# mppt_charger_sch.net
KiCad netlist of a schematic drawn in Altium Designer
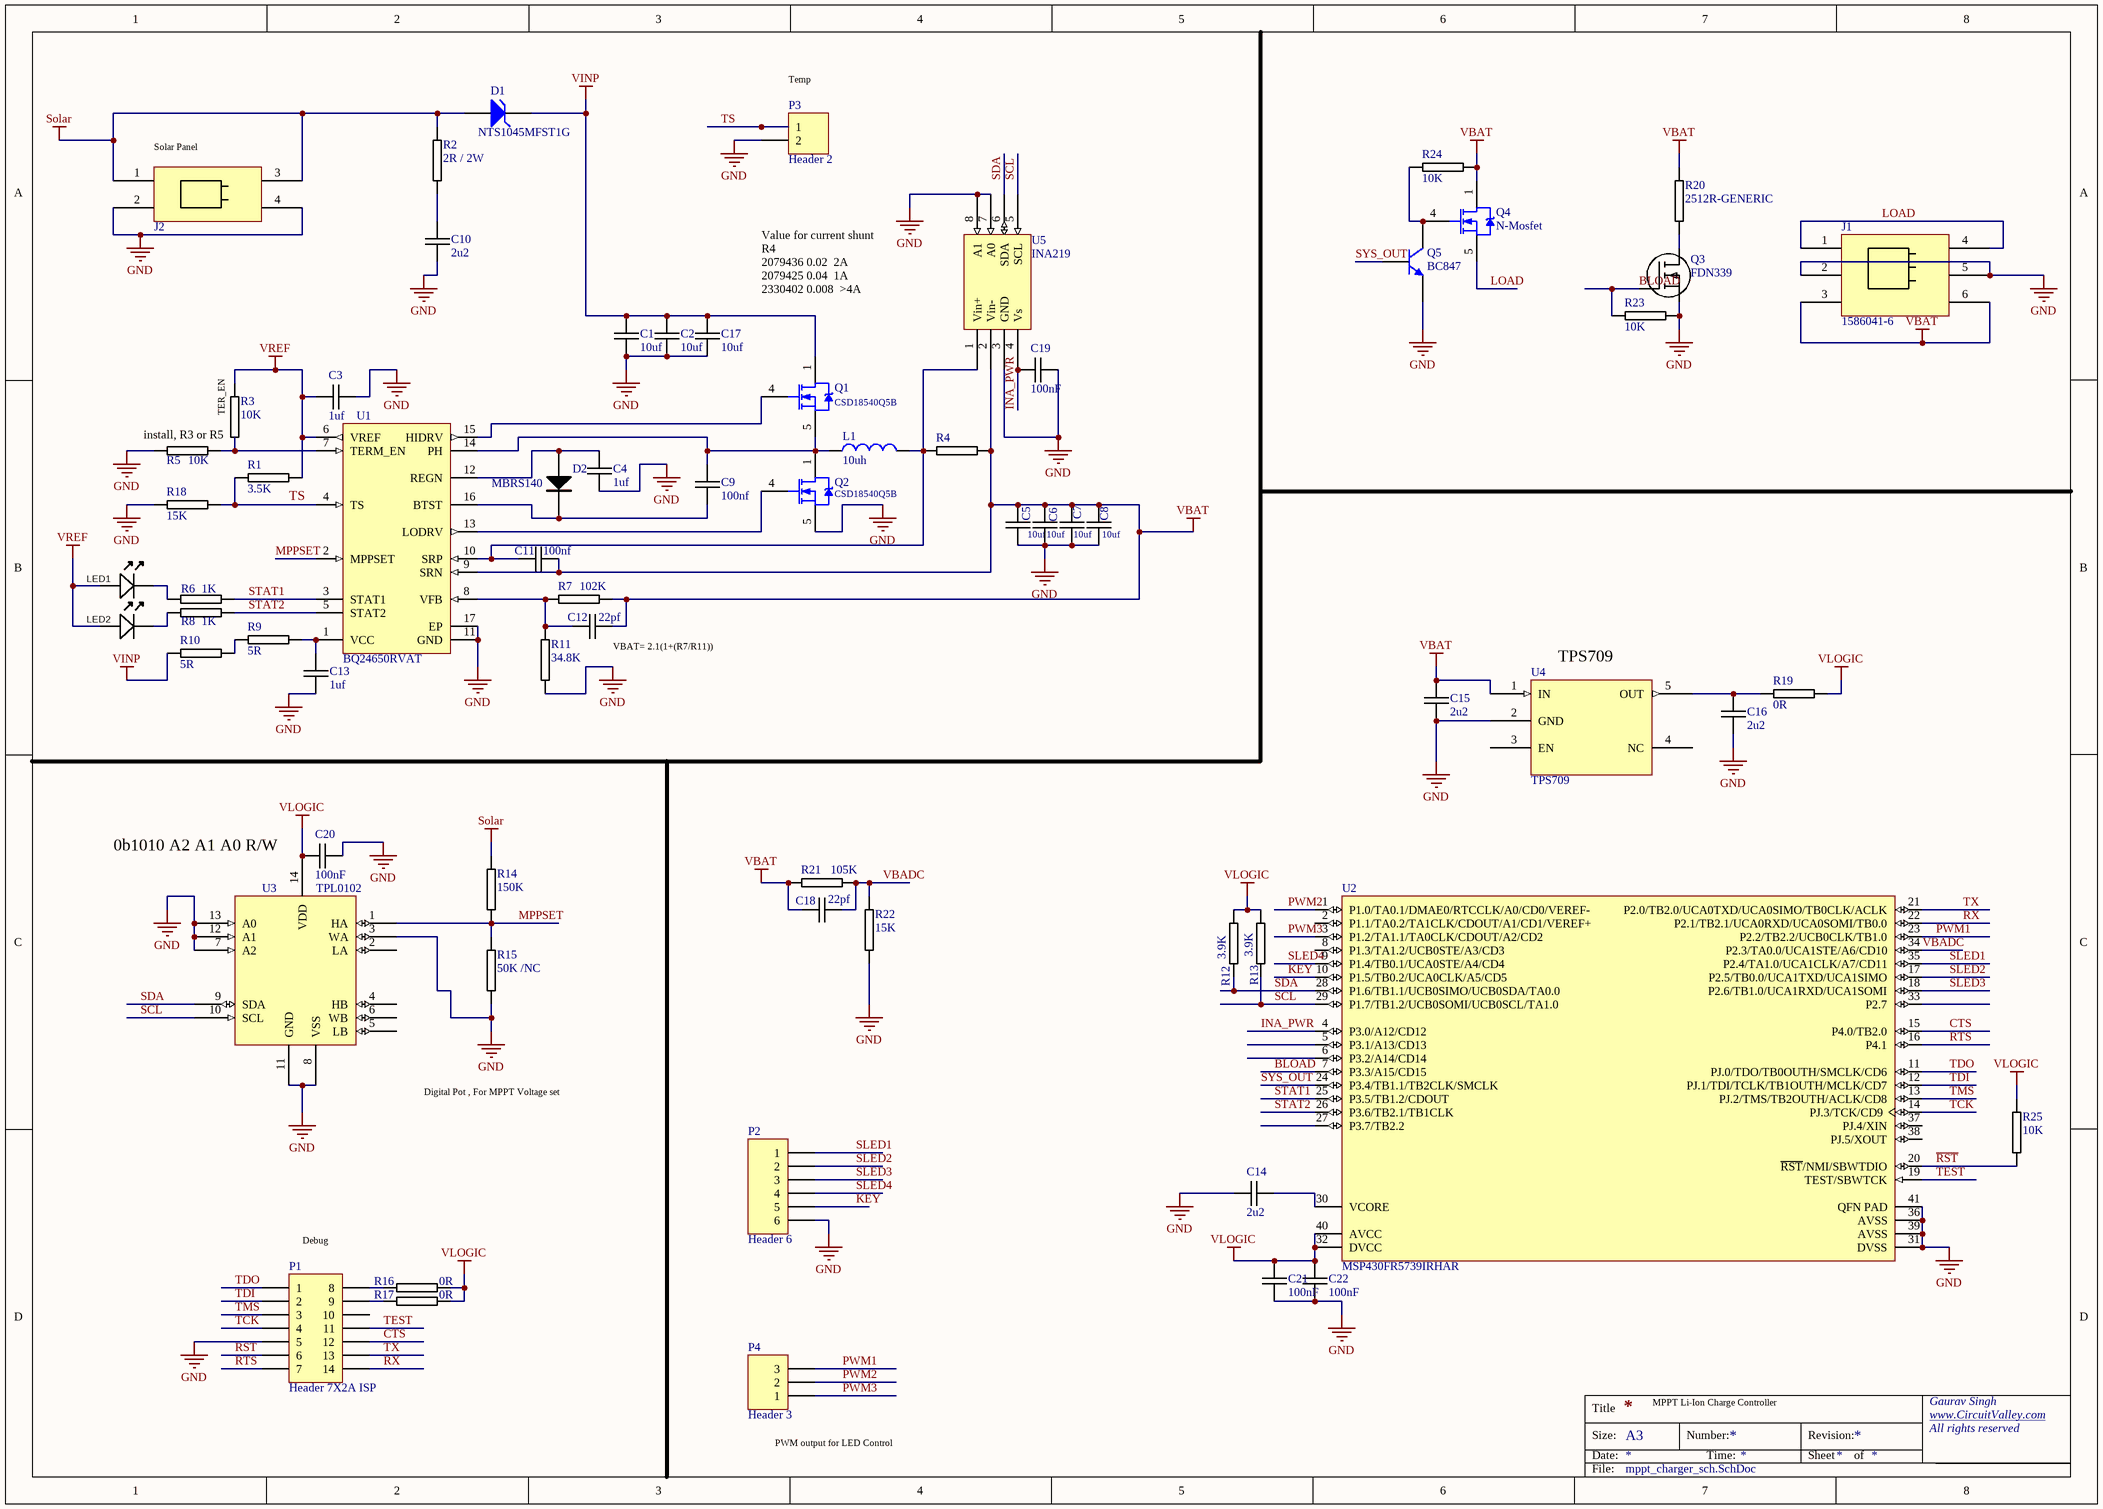
[diagram p0: mppt_charger_sch.SchDoc]

(export (version "E")
  (design (tool "Eeschema 10.0.6"))
  (components
    (comp (ref "C1")
      (value "10uf")
      (footprint "1210C-GENERIC")
      (description "GENERIC CAPACITOR NON POLARISED 1210")
      (fields
        (field (name "MANUFACTURER") "Panasonic - ECG")
        (field (name "MANUFACTURER PART NUMBER") "ECJ-4YB0J226M")
      )
      (libsource (lib "Generic") (part "1210C-2u2-35V"))
    )
    (comp (ref "C2")
      (value "10uf")
      (footprint "1210C-GENERIC")
      (description "GENERIC CAPACITOR NON POLARISED 1210")
      (fields
        (field (name "MANUFACTURER") "Panasonic - ECG")
        (field (name "MANUFACTURER PART NUMBER") "ECJ-4YB0J226M")
      )
      (libsource (lib "Generic") (part "1210C-2u2-35V"))
    )
    (comp (ref "C3")
      (value "1uf")
      (footprint "0805C-GENERIC")
      (description "CAPACITOR 0805 CERAMIC")
      (fields
        (field (name "MANUFACTURER PART NUMBER") "ECJ-1VB0J225K")
        (field (name "MANUFACTURER") "Panasonic - ECG")
      )
      (libsource (lib "Generic") (part "0805C-2U2-6V3-X5R-PAN"))
    )
    (comp (ref "C4")
      (value "1uf")
      (footprint "0805C-GENERIC")
      (description "CAPACITOR 0805 CERAMIC")
      (fields
        (field (name "MANUFACTURER PART NUMBER") "ECJ-1VB0J225K")
        (field (name "MANUFACTURER") "Panasonic - ECG")
      )
      (libsource (lib "Generic") (part "0805C-2U2-6V3-X5R-PAN"))
    )
    (comp (ref "C5")
      (value "10uf")
      (footprint "1210C-GENERIC")
      (description "GENERIC CAPACITOR NON POLARISED 1210")
      (fields
        (field (name "MANUFACTURER") "Panasonic - ECG")
        (field (name "MANUFACTURER PART NUMBER") "ECJ-4YB0J226M")
      )
      (libsource (lib "Generic") (part "1210C-2u2-35V"))
    )
    (comp (ref "C6")
      (value "10uf")
      (footprint "1210C-GENERIC")
      (description "GENERIC CAPACITOR NON POLARISED 1210")
      (fields
        (field (name "MANUFACTURER") "Panasonic - ECG")
        (field (name "MANUFACTURER PART NUMBER") "ECJ-4YB0J226M")
      )
      (libsource (lib "Generic") (part "1210C-2u2-35V"))
    )
    (comp (ref "C7")
      (value "10uf")
      (footprint "1210C-GENERIC")
      (description "GENERIC CAPACITOR NON POLARISED 1210")
      (fields
        (field (name "MANUFACTURER") "Panasonic - ECG")
        (field (name "MANUFACTURER PART NUMBER") "ECJ-4YB0J226M")
      )
      (libsource (lib "Generic") (part "1210C-2u2-35V"))
    )
    (comp (ref "C8")
      (value "10uf")
      (footprint "1210C-GENERIC")
      (description "GENERIC CAPACITOR NON POLARISED 1210")
      (fields
        (field (name "MANUFACTURER") "Panasonic - ECG")
        (field (name "MANUFACTURER PART NUMBER") "ECJ-4YB0J226M")
      )
      (libsource (lib "Generic") (part "1210C-2u2-35V"))
    )
    (comp (ref "C9")
      (value "100nf")
      (footprint "0805C-GENERIC")
      (description "CAPACITOR 0805 CERAMIC")
      (fields
        (field (name "MANUFACTURER PART NUMBER") "ECJ-1VB0J225K")
        (field (name "MANUFACTURER") "Panasonic - ECG")
      )
      (libsource (lib "Generic") (part "0805C-2U2-6V3-X5R-PAN"))
    )
    (comp (ref "C10")
      (value "2u2")
      (footprint "1210C-GENERIC")
      (description "GENERIC CAPACITOR NON POLARISED 1210")
      (fields
        (field (name "MANUFACTURER") "Panasonic - ECG")
        (field (name "MANUFACTURER PART NUMBER") "ECJ-4YB0J226M")
      )
      (libsource (lib "Generic") (part "1210C-2u2-35V"))
    )
    (comp (ref "C11")
      (value "100nf")
      (footprint "0805C-GENERIC")
      (description "CAPACITOR 0805 CERAMIC")
      (fields
        (field (name "MANUFACTURER PART NUMBER") "ECJ-1VB0J225K")
        (field (name "MANUFACTURER") "Panasonic - ECG")
      )
      (libsource (lib "Generic") (part "0805C-2U2-6V3-X5R-PAN"))
    )
    (comp (ref "C12")
      (value "22pf")
      (footprint "0805C-GENERIC")
      (description "CAPACITOR 0805 CERAMIC")
      (fields
        (field (name "MANUFACTURER PART NUMBER") "ECJ-1VB0J225K")
        (field (name "MANUFACTURER") "Panasonic - ECG")
      )
      (libsource (lib "Generic") (part "0805C-2U2-6V3-X5R-PAN"))
    )
    (comp (ref "C13")
      (value "1uf")
      (footprint "0805C-TBD")
      (description "CAPACITOR 0805 CERAMIC VALUE TO BE DETERMINED")
      (libsource (lib "Generic") (part "0805C-TBD"))
    )
    (comp (ref "C14")
      (value "2u2")
      (footprint "0805C-GENERIC")
      (description "CAPACITOR 0805 CERAMIC")
      (fields
        (field (name "MANUFACTURER PART NUMBER") "ECJ-1VB0J225K")
        (field (name "MANUFACTURER") "Panasonic - ECG")
      )
      (libsource (lib "Generic") (part "0805C-2U2-6V3-X5R-PAN"))
    )
    (comp (ref "C15")
      (value "2u2")
      (footprint "1210C-GENERIC")
      (description "GENERIC CAPACITOR NON POLARISED 1210")
      (fields
        (field (name "MANUFACTURER") "Panasonic - ECG")
        (field (name "MANUFACTURER PART NUMBER") "ECJ-4YB0J226M")
      )
      (libsource (lib "Generic") (part "1210C-2u2-35V"))
    )
    (comp (ref "C16")
      (value "2u2")
      (footprint "1210C-GENERIC")
      (description "GENERIC CAPACITOR NON POLARISED 1210")
      (fields
        (field (name "MANUFACTURER") "Panasonic - ECG")
        (field (name "MANUFACTURER PART NUMBER") "ECJ-4YB0J226M")
      )
      (libsource (lib "Generic") (part "1210C-2u2-35V"))
    )
    (comp (ref "C17")
      (value "10uf")
      (footprint "1210C-GENERIC")
      (description "GENERIC CAPACITOR NON POLARISED 1210")
      (fields
        (field (name "MANUFACTURER") "Panasonic - ECG")
        (field (name "MANUFACTURER PART NUMBER") "ECJ-4YB0J226M")
      )
      (libsource (lib "Generic") (part "1210C-2u2-35V"))
    )
    (comp (ref "C18")
      (value "22pf")
      (footprint "0805C-GENERIC")
      (description "CAPACITOR 0805 CERAMIC")
      (fields
        (field (name "MANUFACTURER PART NUMBER") "ECJ-1VB0J225K")
        (field (name "MANUFACTURER") "Panasonic - ECG")
      )
      (libsource (lib "Generic") (part "0805C-2U2-6V3-X5R-PAN"))
    )
    (comp (ref "C19")
      (value "100nF")
      (footprint "0603C-GENERIC")
      (description "CAPACITOR 0603 CERAMIC")
      (fields
        (field (name "MANUFACTURER PART NUMBER") "C1608X7R1E104K")
        (field (name "MANUFACTURER") "TDK Corporation")
      )
      (libsource (lib "Generic") (part "0603C-100NF-25V-X7R-TDK"))
    )
    (comp (ref "C20")
      (value "100nF")
      (footprint "0603C-GENERIC")
      (description "CAPACITOR 0603 CERAMIC")
      (fields
        (field (name "MANUFACTURER PART NUMBER") "C1608X7R1E104K")
        (field (name "MANUFACTURER") "TDK Corporation")
      )
      (libsource (lib "Generic") (part "0603C-100NF-25V-X7R-TDK"))
    )
    (comp (ref "C21")
      (value "100nF")
      (footprint "0603C-GENERIC")
      (description "CAPACITOR 0603 CERAMIC")
      (fields
        (field (name "MANUFACTURER PART NUMBER") "C1608X7R1E104K")
        (field (name "MANUFACTURER") "TDK Corporation")
      )
      (libsource (lib "Generic") (part "0603C-100NF-25V-X7R-TDK"))
    )
    (comp (ref "C22")
      (value "100nF")
      (footprint "0603C-GENERIC")
      (description "CAPACITOR 0603 CERAMIC")
      (fields
        (field (name "MANUFACTURER PART NUMBER") "C1608X7R1E104K")
        (field (name "MANUFACTURER") "TDK Corporation")
      )
      (libsource (lib "Generic") (part "0603C-100NF-25V-X7R-TDK"))
    )
    (comp (ref "D1") (value "NTS1045MFST1G") (footprint "DFN5_5x6") (libsource (lib "diode") (part "SK3200")))
    (comp (ref "D2")
      (value "MBRS140")
      (footprint "DIODE-SMA")
      (description "DIODE")
      (libsource (lib "Generic") (part "MBRS140"))
    )
    (comp (ref "J1")
      (value "1586041-6")
      (footprint "1586043-6")
      (libsource (lib "power_connector") (part "1586041-6"))
    )
    (comp (ref "J2")
      (value "1586041-4")
      (footprint "1586043-4")
      (libsource (lib "power_connector") (part "1586041-4"))
    )
    (comp (ref "L1") (value "10uh") (footprint "SRP1238A") (libsource (lib "Inductor") (part "inductor_smd")))
    (comp (ref "LED1")
      (value "~")
      (footprint "LED-0805-K")
      (description "LED, 0805 SMD, Green")
      (libsource (lib "PBL - Light Sources") (part "LED_SMD_Green_0805"))
    )
    (comp (ref "LED2")
      (value "~")
      (footprint "LED-0805-K")
      (description "LED, 0805 SMD, Green")
      (libsource (lib "PBL - Light Sources") (part "LED_SMD_Green_0805"))
    )
    (comp (ref "P1")
      (value "Header 7X2A ISP")
      (footprint "HDR2X7_CEN")
      (description "Header, 7-Pin, Dual row")
      (fields (field (name "PUBLISHER") "Altium Limited"))
      (libsource (lib "Miscellaneous Connectors") (part "Header 7X2A"))
    )
    (comp (ref "P2")
      (value "Header 6")
      (footprint "5267-06A")
      (description "Header, 6-Pin")
      (fields (field (name "PUBLISHER") "Altium Limited"))
      (libsource (lib "Miscellaneous Connectors") (part "Header 6"))
    )
    (comp (ref "P3")
      (value "Header 2")
      (footprint "5267-02A")
      (description "Header, 2-Pin")
      (fields (field (name "PUBLISHER") "Altium Limited"))
      (libsource (lib "Miscellaneous Connectors") (part "Header 2"))
    )
    (comp (ref "P4")
      (value "Header 3")
      (footprint "5267-03A")
      (description "Header, 3-Pin")
      (fields (field (name "PUBLISHER") "Altium Limited"))
      (libsource (lib "Miscellaneous Connectors") (part "Header 3"))
    )
    (comp (ref "Q1") (value "CSD18540Q5B") (footprint "SON8") (libsource (lib "mosfet") (part "N-Mosfet")))
    (comp (ref "Q2") (value "CSD18540Q5B") (footprint "SON8") (libsource (lib "mosfet") (part "N-Mosfet")))
    (comp (ref "Q3")
      (value "FDN339")
      (footprint "SOT23-GDS")
      (description "N-MOS TRANSISTOR FDN339")
      (fields
        (field (name "MANUFACTURER") "Fairchild Semiconductor")
        (field (name "MANUFACTURER PART NUMBER") "FDN339AN")
      )
      (libsource (lib "Generic") (part "FDN339"))
    )
    (comp (ref "Q4") (value "N-Mosfet") (footprint "SON8") (libsource (lib "mosfet") (part "N-Mosfet")))
    (comp (ref "Q5")
      (value "BC847")
      (footprint "SOT23_N")
      (description "NPN General-purpose Transistor")
      (fields (field (name "PUBLISHER") "Altium Limited"))
      (libsource (lib "Philips Discrete BJT - Low Power") (part "BC847"))
    )
    (comp (ref "R1")
      (value "3.5K")
      (footprint "0805R-2K2")
      (description "RESISTOR 0805 1/4 WATT THIN FILM")
      (libsource (lib "Generic") (part "0805R-2K2"))
    )
    (comp (ref "R2")
      (value "2R / 2W")
      (footprint "2512R-GENERIC")
      (description "GENERIC RESISTOR 2512")
      (libsource (lib "Generic") (part "2512R-GENERIC"))
    )
    (comp (ref "R3")
      (value "10K")
      (footprint "0805R-2K2")
      (description "RESISTOR 0805 1/4 WATT THIN FILM")
      (libsource (lib "Generic") (part "0805R-2K2"))
    )
    (comp (ref "R4")
      (value "~")
      (footprint "2512R-GENERIC")
      (description "GENERIC RESISTOR 2512")
      (libsource (lib "Generic") (part "2512R-GENERIC"))
    )
    (comp (ref "R5")
      (value "10K")
      (footprint "0805R-2K2")
      (description "RESISTOR 0805 1/4 WATT THIN FILM")
      (libsource (lib "Generic") (part "0805R-2K2"))
    )
    (comp (ref "R6")
      (value "1K")
      (footprint "0805R-2K2")
      (description "RESISTOR 0805 1/4 WATT THIN FILM")
      (libsource (lib "Generic") (part "0805R-2K2"))
    )
    (comp (ref "R7")
      (value "102K")
      (footprint "0805R-2K2")
      (description "RESISTOR 0805 1/4 WATT THIN FILM")
      (libsource (lib "Generic") (part "0805R-2K2"))
    )
    (comp (ref "R8")
      (value "1K")
      (footprint "0805R-2K2")
      (description "RESISTOR 0805 1/4 WATT THIN FILM")
      (libsource (lib "Generic") (part "0805R-2K2"))
    )
    (comp (ref "R9")
      (value "5R")
      (footprint "0805R-2K2")
      (description "RESISTOR 0805 1/4 WATT THIN FILM")
      (libsource (lib "Generic") (part "0805R-2K2"))
    )
    (comp (ref "R10")
      (value "5R")
      (footprint "0805R-2K2")
      (description "RESISTOR 0805 1/4 WATT THIN FILM")
      (libsource (lib "Generic") (part "0805R-2K2"))
    )
    (comp (ref "R11")
      (value "34.8K")
      (footprint "0805R-2K2")
      (description "RESISTOR 0805 1/4 WATT THIN FILM")
      (libsource (lib "Generic") (part "0805R-2K2"))
    )
    (comp (ref "R12")
      (value "3.9K")
      (footprint "0805R-2K2")
      (description "RESISTOR 0805 1/4 WATT THIN FILM")
      (libsource (lib "Generic") (part "0805R-2K2"))
    )
    (comp (ref "R13")
      (value "3.9K")
      (footprint "0805R-2K2")
      (description "RESISTOR 0805 1/4 WATT THIN FILM")
      (libsource (lib "Generic") (part "0805R-2K2"))
    )
    (comp (ref "R14")
      (value "150K")
      (footprint "0805R-2K2")
      (description "RESISTOR 0805 1/4 WATT THIN FILM")
      (libsource (lib "Generic") (part "0805R-2K2"))
    )
    (comp (ref "R15")
      (value "50K /NC")
      (footprint "0805R-2K2")
      (description "RESISTOR 0805 1/4 WATT THIN FILM")
      (libsource (lib "Generic") (part "0805R-2K2"))
    )
    (comp (ref "R16")
      (value "0R")
      (footprint "0805R-2K2")
      (description "RESISTOR 0805 1/4 WATT THIN FILM")
      (libsource (lib "Generic") (part "0805R-2K2"))
    )
    (comp (ref "R17")
      (value "0R")
      (footprint "0805R-2K2")
      (description "RESISTOR 0805 1/4 WATT THIN FILM")
      (libsource (lib "Generic") (part "0805R-2K2"))
    )
    (comp (ref "R18")
      (value "15K")
      (footprint "0805R-2K2")
      (description "RESISTOR 0805 1/4 WATT THIN FILM")
      (libsource (lib "Generic") (part "0805R-2K2"))
    )
    (comp (ref "R19")
      (value "0R")
      (footprint "0805R-2K2")
      (description "RESISTOR 0805 1/4 WATT THIN FILM")
      (libsource (lib "Generic") (part "0805R-2K2"))
    )
    (comp (ref "R20")
      (value "2512R-GENERIC")
      (footprint "2512R-GENERIC")
      (description "GENERIC RESISTOR 2512")
      (libsource (lib "Generic") (part "2512R-GENERIC"))
    )
    (comp (ref "R21")
      (value "105K")
      (footprint "0805R-2K2")
      (description "RESISTOR 0805 1/4 WATT THIN FILM")
      (libsource (lib "Generic") (part "0805R-2K2"))
    )
    (comp (ref "R22")
      (value "15K")
      (footprint "0805R-2K2")
      (description "RESISTOR 0805 1/4 WATT THIN FILM")
      (libsource (lib "Generic") (part "0805R-2K2"))
    )
    (comp (ref "R23")
      (value "10K")
      (footprint "0603R-10K")
      (description "GENERIC RESISTOR 0603")
      (fields (field (name "MANUFACTURER") "Stackpole Electronics Inc") (field (name "TOLERANCE") "±1%"))
      (libsource (lib "Generic") (part "0603R-10K"))
    )
    (comp (ref "R24")
      (value "10K")
      (footprint "0603R-10K")
      (description "GENERIC RESISTOR 0603")
      (fields (field (name "MANUFACTURER") "Stackpole Electronics Inc") (field (name "TOLERANCE") "±1%"))
      (libsource (lib "Generic") (part "0603R-10K"))
    )
    (comp (ref "R25")
      (value "10K")
      (footprint "0603R-10K")
      (description "GENERIC RESISTOR 0603")
      (fields (field (name "MANUFACTURER") "Stackpole Electronics Inc") (field (name "TOLERANCE") "±1%"))
      (libsource (lib "Generic") (part "0603R-10K"))
    )
    (comp (ref "U1")
      (value "BQ24650RVAT")
      (footprint "QFN16")
      (fields (field (name "MANUFACTURER") "Texas Instruments"))
      (libsource (lib "TI Power Management Battery Management") (part "BQ24650RVAT"))
    )
    (comp (ref "U2")
      (value "MSP430FR5739IRHAR")
      (footprint "QFN40")
      (fields (field (name "MANUFACTURER") "Texas Instruments"))
      (libsource (lib "TI Microcontroller MSP430 16-bit Ultra-Low Power") (part "MSP430FR5739IRHAR"))
    )
    (comp (ref "U3")
      (value "TPL0102")
      (footprint "XQFN14_2mmx2mm")
      (description "Digital Pot 2 channel 256 setp nov volatile memeory")
      (libsource (lib "digital_pot") (part "TPL0102"))
    )
    (comp (ref "U4") (value "TPS709") (footprint "SOT23-5") (libsource (lib "LDO_reg") (part "TPS709")))
    (comp (ref "U5")
      (value "INA219")
      (footprint "SOT23-8")
      (libsource (lib "INA219-SOT23-8") (part "INA219"))
    )
  )
  (nets
    (net (code "1") (name "/BLOAD") (class "Default")
      (node (ref "Q3") (pin "G") (pinfunction "G_G") (pintype "passive"))
      (node (ref "R23") (pin "2") (pintype "passive"))
      (node (ref "U2") (pin "7") (pinfunction "P3.3/A15/CD15_7") (pintype "bidirectional"))
    )
    (net (code "2") (name "/CTS") (class "Default")
      (node (ref "P1") (pin "12") (pinfunction "12_12") (pintype "passive"))
      (node (ref "U2") (pin "15") (pinfunction "P4.0/TB2.0_15") (pintype "bidirectional"))
    )
    (net (code "3") (name "/INA_PWR") (class "Default")
      (node (ref "C19") (pin "2") (pintype "passive"))
      (node (ref "U2") (pin "4") (pinfunction "P3.0/A12/CD12_4") (pintype "bidirectional"))
      (node (ref "U5") (pin "4") (pinfunction "Vs_4") (pintype "power_in"))
    )
    (net (code "4") (name "/KEY") (class "Default")
      (node (ref "P2") (pin "5") (pinfunction "5_5") (pintype "passive"))
      (node (ref "U2") (pin "10") (pinfunction "P1.5/TB0.2/UCA0CLK/A5/CD5_10") (pintype "bidirectional"))
    )
    (net (code "5") (name "/LOAD") (class "Default")
      (node (ref "J1") (pin "1") (pinfunction "IN_1") (pintype "passive"))
      (node (ref "J1") (pin "4") (pinfunction "IN_4") (pintype "passive"))
      (node (ref "Q4") (pin "5") (pinfunction "S_5") (pintype "passive"))
    )
    (net (code "6") (name "/MPPSET") (class "Default")
      (node (ref "R14") (pin "1") (pintype "passive"))
      (node (ref "R15") (pin "2") (pintype "passive"))
      (node (ref "U1") (pin "2") (pinfunction "MPPSET_2") (pintype "input"))
      (node (ref "U3") (pin "1") (pinfunction "HA_1") (pintype "bidirectional"))
    )
    (net (code "7") (name "/PWM1") (class "Default")
      (node (ref "P4") (pin "3") (pinfunction "3_3") (pintype "passive"))
      (node (ref "U2") (pin "23") (pinfunction "P2.2/TB2.2/UCB0CLK/TB1.0_23") (pintype "bidirectional"))
    )
    (net (code "8") (name "/PWM2") (class "Default")
      (node (ref "P4") (pin "2") (pinfunction "2_2") (pintype "passive"))
      (node (ref "U2") (pin "1") (pinfunction "P1.0/TA0.1/DMAE0/RTCCLK/A0/CD0/VEREF-_1") (pintype "bidirectional"))
    )
    (net (code "9") (name "/PWM3") (class "Default")
      (node (ref "P4") (pin "1") (pinfunction "1_1") (pintype "passive"))
      (node (ref "U2") (pin "3") (pinfunction "P1.2/TA1.1/TA0CLK/CDOUT/A2/CD2_3") (pintype "bidirectional"))
    )
    (net (code "10") (name "/RTS") (class "Default")
      (node (ref "P1") (pin "7") (pinfunction "7_7") (pintype "passive"))
      (node (ref "U2") (pin "16") (pinfunction "P4.1_16") (pintype "bidirectional"))
    )
    (net (code "11") (name "/RX") (class "Default")
      (node (ref "P1") (pin "14") (pinfunction "14_14") (pintype "passive"))
      (node (ref "U2") (pin "22") (pinfunction "P2.1/TB2.1/UCA0RXD/UCA0SOMI/TB0.0_22") (pintype "bidirectional"))
    )
    (net (code "12") (name "/SCL") (class "Default")
      (node (ref "R13") (pin "1") (pintype "passive"))
      (node (ref "U2") (pin "29") (pinfunction "P1.7/TB1.2/UCB0SOMI/UCB0SCL/TA1.0_29") (pintype "bidirectional"))
      (node (ref "U3") (pin "10") (pinfunction "SCL_10") (pintype "input"))
      (node (ref "U5") (pin "5") (pinfunction "SCL_5") (pintype "input"))
    )
    (net (code "13") (name "/SDA") (class "Default")
      (node (ref "R12") (pin "1") (pintype "passive"))
      (node (ref "U2") (pin "28") (pinfunction "P1.6/TB1.1/UCB0SIMO/UCB0SDA/TA0.0_28") (pintype "bidirectional"))
      (node (ref "U3") (pin "9") (pinfunction "SDA_9") (pintype "bidirectional"))
      (node (ref "U5") (pin "6") (pinfunction "SDA_6") (pintype "bidirectional"))
    )
    (net (code "14") (name "/SLED1") (class "Default")
      (node (ref "P2") (pin "1") (pinfunction "1_1") (pintype "passive"))
      (node (ref "U2") (pin "35") (pinfunction "P2.4/TA1.0/UCA1CLK/A7/CD11_35") (pintype "bidirectional"))
    )
    (net (code "15") (name "/SLED2") (class "Default")
      (node (ref "P2") (pin "2") (pinfunction "2_2") (pintype "passive"))
      (node (ref "U2") (pin "17") (pinfunction "P2.5/TB0.0/UCA1TXD/UCA1SIMO_17") (pintype "bidirectional"))
    )
    (net (code "16") (name "/SLED3") (class "Default")
      (node (ref "P2") (pin "3") (pinfunction "3_3") (pintype "passive"))
      (node (ref "U2") (pin "18") (pinfunction "P2.6/TB1.0/UCA1RXD/UCA1SOMI_18") (pintype "bidirectional"))
    )
    (net (code "17") (name "/SLED4") (class "Default")
      (node (ref "P2") (pin "4") (pinfunction "4_4") (pintype "passive"))
      (node (ref "U2") (pin "9") (pinfunction "P1.4/TB0.1/UCA0STE/A4/CD4_9") (pintype "bidirectional"))
    )
    (net (code "18") (name "/STAT1") (class "Default")
      (node (ref "R6") (pin "2") (pintype "passive"))
      (node (ref "U1") (pin "3") (pinfunction "STAT1_3") (pintype "open_collector"))
      (node (ref "U2") (pin "25") (pinfunction "P3.5/TB1.2/CDOUT_25") (pintype "bidirectional"))
    )
    (net (code "19") (name "/STAT2") (class "Default")
      (node (ref "R8") (pin "2") (pintype "passive"))
      (node (ref "U1") (pin "5") (pinfunction "STAT2_5") (pintype "open_collector"))
      (node (ref "U2") (pin "26") (pinfunction "P3.6/TB2.1/TB1CLK_26") (pintype "bidirectional"))
    )
    (net (code "20") (name "/SYS_OUT") (class "Default")
      (node (ref "Q5") (pin "1") (pinfunction "B_1") (pintype "passive"))
      (node (ref "U2") (pin "24") (pinfunction "P3.4/TB1.1/TB2CLK/SMCLK_24") (pintype "bidirectional"))
    )
    (net (code "21") (name "/TCK") (class "Default")
      (node (ref "P1") (pin "4") (pinfunction "4_4") (pintype "passive"))
      (node (ref "U2") (pin "14") (pinfunction "PJ.3/TCK/CD9_14") (pintype "bidirectional"))
    )
    (net (code "22") (name "/TDI") (class "Default")
      (node (ref "P1") (pin "2") (pinfunction "2_2") (pintype "passive"))
      (node (ref "U2") (pin "12") (pinfunction "PJ.1/TDI/TCLK/TB1OUTH/MCLK/CD7_12") (pintype "bidirectional"))
    )
    (net (code "23") (name "/TDO") (class "Default")
      (node (ref "P1") (pin "1") (pinfunction "1_1") (pintype "passive"))
      (node (ref "U2") (pin "11") (pinfunction "PJ.0/TDO/TB0OUTH/SMCLK/CD6_11") (pintype "bidirectional"))
    )
    (net (code "24") (name "/TEST") (class "Default")
      (node (ref "P1") (pin "11") (pinfunction "11_11") (pintype "passive"))
      (node (ref "U2") (pin "19") (pinfunction "TEST/SBWTCK_19") (pintype "input"))
    )
    (net (code "25") (name "/TMS") (class "Default")
      (node (ref "P1") (pin "3") (pinfunction "3_3") (pintype "passive"))
      (node (ref "U2") (pin "13") (pinfunction "PJ.2/TMS/TB2OUTH/ACLK/CD8_13") (pintype "bidirectional"))
    )
    (net (code "26") (name "/TS") (class "Default")
      (node (ref "P3") (pin "1") (pinfunction "1_1") (pintype "passive"))
      (node (ref "R1") (pin "2") (pintype "passive"))
      (node (ref "R18") (pin "1") (pintype "passive"))
      (node (ref "U1") (pin "4") (pinfunction "TS_4") (pintype "input"))
    )
    (net (code "27") (name "/TX") (class "Default")
      (node (ref "P1") (pin "13") (pinfunction "13_13") (pintype "passive"))
      (node (ref "U2") (pin "21") (pinfunction "P2.0/TB2.0/UCA0TXD/UCA0SIMO/TB0CLK/ACLK_21") (pintype "bidirectional"))
    )
    (net (code "28") (name "/VBADC") (class "Default")
      (node (ref "C18") (pin "1") (pintype "passive"))
      (node (ref "R21") (pin "2") (pintype "passive"))
      (node (ref "R22") (pin "2") (pintype "passive"))
      (node (ref "U2") (pin "34") (pinfunction "P2.3/TA0.0/UCA1STE/A6/CD10_34") (pintype "bidirectional"))
    )
    (net (code "29") (name "/~{RST}") (class "Default")
      (node (ref "P1") (pin "6") (pinfunction "6_6") (pintype "passive"))
      (node (ref "R25") (pin "2") (pintype "passive"))
      (node (ref "U2") (pin "20") (pinfunction "~{RST}/NMI/SBWTDIO_20") (pintype "bidirectional"))
    )
    (net (code "30") (name "GND") (class "Default")
      (node (ref "C1") (pin "2") (pintype "passive"))
      (node (ref "C10") (pin "2") (pintype "passive"))
      (node (ref "C13") (pin "2") (pintype "passive"))
      (node (ref "C14") (pin "1") (pintype "passive"))
      (node (ref "C15") (pin "2") (pintype "passive"))
      (node (ref "C16") (pin "2") (pintype "passive"))
      (node (ref "C17") (pin "2") (pintype "passive"))
      (node (ref "C19") (pin "1") (pintype "passive"))
      (node (ref "C2") (pin "2") (pintype "passive"))
      (node (ref "C20") (pin "2") (pintype "passive"))
      (node (ref "C21") (pin "2") (pintype "passive"))
      (node (ref "C22") (pin "2") (pintype "passive"))
      (node (ref "C3") (pin "2") (pintype "passive"))
      (node (ref "C4") (pin "2") (pintype "passive"))
      (node (ref "C5") (pin "2") (pintype "passive"))
      (node (ref "C6") (pin "2") (pintype "passive"))
      (node (ref "C7") (pin "2") (pintype "passive"))
      (node (ref "C8") (pin "2") (pintype "passive"))
      (node (ref "J1") (pin "2") (pinfunction "IN_2") (pintype "passive"))
      (node (ref "J1") (pin "5") (pinfunction "5_5") (pintype "passive"))
      (node (ref "J2") (pin "2") (pinfunction "IN_2") (pintype "passive"))
      (node (ref "J2") (pin "4") (pinfunction "IN_4") (pintype "passive"))
      (node (ref "P1") (pin "5") (pinfunction "5_5") (pintype "passive"))
      (node (ref "P2") (pin "6") (pinfunction "6_6") (pintype "passive"))
      (node (ref "P3") (pin "2") (pinfunction "2_2") (pintype "passive"))
      (node (ref "Q2") (pin "5") (pinfunction "S_5") (pintype "passive"))
      (node (ref "Q3") (pin "S") (pinfunction "S_S") (pintype "passive"))
      (node (ref "Q5") (pin "2") (pinfunction "E_2") (pintype "passive"))
      (node (ref "R11") (pin "1") (pintype "passive"))
      (node (ref "R15") (pin "1") (pintype "passive"))
      (node (ref "R18") (pin "2") (pintype "passive"))
      (node (ref "R22") (pin "1") (pintype "passive"))
      (node (ref "R23") (pin "1") (pintype "passive"))
      (node (ref "R5") (pin "1") (pintype "passive"))
      (node (ref "U1") (pin "11") (pinfunction "GND_11") (pintype "power_in"))
      (node (ref "U1") (pin "17") (pinfunction "EP_17") (pintype "power_in"))
      (node (ref "U2") (pin "31") (pinfunction "DVSS_31") (pintype "power_in"))
      (node (ref "U2") (pin "36") (pinfunction "AVSS_36") (pintype "power_in"))
      (node (ref "U2") (pin "39") (pinfunction "AVSS_39") (pintype "power_in"))
      (node (ref "U2") (pin "41") (pinfunction "QFN_PAD_41") (pintype "power_in"))
      (node (ref "U3") (pin "11") (pinfunction "GND_11") (pintype "power_in"))
      (node (ref "U3") (pin "12") (pinfunction "A1_12") (pintype "input"))
      (node (ref "U3") (pin "13") (pinfunction "A0_13") (pintype "input"))
      (node (ref "U3") (pin "3") (pinfunction "WA_3") (pintype "bidirectional"))
      (node (ref "U3") (pin "7") (pinfunction "A2_7") (pintype "input"))
      (node (ref "U3") (pin "8") (pinfunction "VSS_8") (pintype "power_in"))
      (node (ref "U4") (pin "2") (pinfunction "GND_2") (pintype "power_in"))
      (node (ref "U5") (pin "3") (pinfunction "GND_3") (pintype "power_in"))
      (node (ref "U5") (pin "7") (pinfunction "A0_7") (pintype "input"))
      (node (ref "U5") (pin "8") (pinfunction "A1_8") (pintype "input"))
    )
    (net (code "31") (name "Net-(C10-Pad1)") (class "Default")
      (node (ref "C10") (pin "1") (pintype "passive"))
      (node (ref "R2") (pin "1") (pintype "passive"))
    )
    (net (code "32") (name "Net-(LED1-PadK)") (class "Default")
      (node (ref "LED1") (pin "K") (pinfunction "K_K") (pintype "passive"))
      (node (ref "R6") (pin "1") (pintype "passive"))
    )
    (net (code "33") (name "Net-(LED2-PadK)") (class "Default")
      (node (ref "LED2") (pin "K") (pinfunction "K_K") (pintype "passive"))
      (node (ref "R8") (pin "1") (pintype "passive"))
    )
    (net (code "34") (name "Net-(P1-Pad8)") (class "Default")
      (node (ref "P1") (pin "8") (pinfunction "8_8") (pintype "passive"))
      (node (ref "R16") (pin "2") (pintype "passive"))
    )
    (net (code "35") (name "Net-(P1-Pad9)") (class "Default")
      (node (ref "P1") (pin "9") (pinfunction "9_9") (pintype "passive"))
      (node (ref "R17") (pin "2") (pintype "passive"))
    )
    (net (code "36") (name "Net-(Q1-G)") (class "Default")
      (node (ref "Q1") (pin "4") (pinfunction "G_4") (pintype "passive"))
      (node (ref "U1") (pin "15") (pinfunction "HIDRV_15") (pintype "output"))
    )
    (net (code "37") (name "Net-(Q1-S)") (class "Default")
      (node (ref "C9") (pin "1") (pintype "passive"))
      (node (ref "L1") (pin "1") (pinfunction "1_1") (pintype "passive"))
      (node (ref "Q1") (pin "5") (pinfunction "S_5") (pintype "passive"))
      (node (ref "Q2") (pin "1") (pinfunction "D_1") (pintype "passive"))
      (node (ref "U1") (pin "14") (pinfunction "PH_14") (pintype "passive"))
    )
    (net (code "38") (name "Net-(Q2-G)") (class "Default")
      (node (ref "Q2") (pin "4") (pinfunction "G_4") (pintype "passive"))
      (node (ref "U1") (pin "13") (pinfunction "LODRV_13") (pintype "output"))
    )
    (net (code "39") (name "Net-(Q3-PadD)") (class "Default")
      (node (ref "Q3") (pin "D") (pinfunction "D_D") (pintype "passive"))
      (node (ref "R20") (pin "1") (pintype "passive"))
    )
    (net (code "40") (name "Net-(Q4-G)") (class "Default")
      (node (ref "Q4") (pin "4") (pinfunction "G_4") (pintype "passive"))
      (node (ref "Q5") (pin "3") (pinfunction "C_3") (pintype "passive"))
      (node (ref "R24") (pin "2") (pintype "passive"))
    )
    (net (code "41") (name "Net-(R10-Pad2)") (class "Default")
      (node (ref "R10") (pin "2") (pintype "passive"))
      (node (ref "R9") (pin "1") (pintype "passive"))
    )
    (net (code "42") (name "Net-(U1-BTST)") (class "Default")
      (node (ref "C9") (pin "2") (pintype "passive"))
      (node (ref "D2") (pin "K") (pinfunction "K_K") (pintype "passive"))
      (node (ref "U1") (pin "16") (pinfunction "BTST_16") (pintype "power_in"))
    )
    (net (code "43") (name "Net-(U1-REGN)") (class "Default")
      (node (ref "C4") (pin "1") (pintype "passive"))
      (node (ref "D2") (pin "A") (pinfunction "A_A") (pintype "passive"))
      (node (ref "U1") (pin "12") (pinfunction "REGN_12") (pintype "power_in"))
    )
    (net (code "44") (name "Net-(U1-SRP)") (class "Default")
      (node (ref "C11") (pin "1") (pintype "passive"))
      (node (ref "L1") (pin "2") (pinfunction "2_2") (pintype "passive"))
      (node (ref "R4") (pin "1") (pintype "passive"))
      (node (ref "U1") (pin "10") (pinfunction "SRP_10") (pintype "input"))
      (node (ref "U5") (pin "1") (pinfunction "Vin+_1") (pintype "passive"))
    )
    (net (code "45") (name "Net-(U1-TERM_EN)") (class "Default")
      (node (ref "R3") (pin "1") (pintype "passive"))
      (node (ref "R5") (pin "2") (pintype "passive"))
      (node (ref "U1") (pin "7") (pinfunction "TERM_EN_7") (pintype "input"))
    )
    (net (code "46") (name "Net-(U1-VCC)") (class "Default")
      (node (ref "C13") (pin "1") (pintype "passive"))
      (node (ref "R9") (pin "2") (pintype "passive"))
      (node (ref "U1") (pin "1") (pinfunction "VCC_1") (pintype "power_in"))
    )
    (net (code "47") (name "Net-(U1-VFB)") (class "Default")
      (node (ref "C12") (pin "1") (pintype "passive"))
      (node (ref "R11") (pin "2") (pintype "passive"))
      (node (ref "R7") (pin "2") (pintype "passive"))
      (node (ref "U1") (pin "8") (pinfunction "VFB_8") (pintype "input"))
    )
    (net (code "48") (name "Net-(U2-VCORE)") (class "Default")
      (node (ref "C14") (pin "2") (pintype "passive"))
      (node (ref "U2") (pin "30") (pinfunction "VCORE_30") (pintype "passive"))
    )
    (net (code "49") (name "Net-(U4-OUT)") (class "Default")
      (node (ref "C16") (pin "1") (pintype "passive"))
      (node (ref "R19") (pin "2") (pintype "passive"))
      (node (ref "U4") (pin "5") (pinfunction "OUT_5") (pintype "output"))
    )
    (net (code "50") (name "Solar") (class "Default")
      (node (ref "D1") (pin "1") (pinfunction "A_1") (pintype "passive"))
      (node (ref "J2") (pin "1") (pinfunction "IN_1") (pintype "passive"))
      (node (ref "J2") (pin "3") (pinfunction "IN_3") (pintype "passive"))
      (node (ref "R14") (pin "2") (pintype "passive"))
      (node (ref "R2") (pin "2") (pintype "passive"))
    )
    (net (code "51") (name "VBAT") (class "Default")
      (node (ref "C11") (pin "2") (pintype "passive"))
      (node (ref "C12") (pin "2") (pintype "passive"))
      (node (ref "C15") (pin "1") (pintype "passive"))
      (node (ref "C18") (pin "2") (pintype "passive"))
      (node (ref "C5") (pin "1") (pintype "passive"))
      (node (ref "C6") (pin "1") (pintype "passive"))
      (node (ref "C7") (pin "1") (pintype "passive"))
      (node (ref "C8") (pin "1") (pintype "passive"))
      (node (ref "J1") (pin "3") (pinfunction "IN_3") (pintype "passive"))
      (node (ref "J1") (pin "6") (pinfunction "6_6") (pintype "passive"))
      (node (ref "Q4") (pin "1") (pinfunction "D_1") (pintype "passive"))
      (node (ref "R20") (pin "2") (pintype "passive"))
      (node (ref "R21") (pin "1") (pintype "passive"))
      (node (ref "R24") (pin "1") (pintype "passive"))
      (node (ref "R4") (pin "2") (pintype "passive"))
      (node (ref "R7") (pin "1") (pintype "passive"))
      (node (ref "U1") (pin "9") (pinfunction "SRN_9") (pintype "input"))
      (node (ref "U4") (pin "1") (pinfunction "IN_1") (pintype "input"))
      (node (ref "U5") (pin "2") (pinfunction "Vin-_2") (pintype "passive"))
    )
    (net (code "52") (name "VINP") (class "Default")
      (node (ref "C1") (pin "1") (pintype "passive"))
      (node (ref "C17") (pin "1") (pintype "passive"))
      (node (ref "C2") (pin "1") (pintype "passive"))
      (node (ref "D1") (pin "2") (pinfunction "K_2") (pintype "passive"))
      (node (ref "Q1") (pin "1") (pinfunction "D_1") (pintype "passive"))
      (node (ref "R10") (pin "1") (pintype "passive"))
    )
    (net (code "53") (name "VLOGIC") (class "Default")
      (node (ref "C20") (pin "1") (pintype "passive"))
      (node (ref "C21") (pin "1") (pintype "passive"))
      (node (ref "C22") (pin "1") (pintype "passive"))
      (node (ref "R12") (pin "2") (pintype "passive"))
      (node (ref "R13") (pin "2") (pintype "passive"))
      (node (ref "R16") (pin "1") (pintype "passive"))
      (node (ref "R17") (pin "1") (pintype "passive"))
      (node (ref "R19") (pin "1") (pintype "passive"))
      (node (ref "R25") (pin "1") (pintype "passive"))
      (node (ref "U2") (pin "32") (pinfunction "DVCC_32") (pintype "power_in"))
      (node (ref "U2") (pin "40") (pinfunction "AVCC_40") (pintype "power_in"))
      (node (ref "U3") (pin "14") (pinfunction "VDD_14") (pintype "power_in"))
    )
    (net (code "54") (name "VREF") (class "Default")
      (node (ref "C3") (pin "1") (pintype "passive"))
      (node (ref "LED1") (pin "A") (pinfunction "A_A") (pintype "passive"))
      (node (ref "LED2") (pin "A") (pinfunction "A_A") (pintype "passive"))
      (node (ref "R1") (pin "1") (pintype "passive"))
      (node (ref "R3") (pin "2") (pintype "passive"))
      (node (ref "U1") (pin "6") (pinfunction "VREF_6") (pintype "output"))
    )
    (net (code "55") (name "unconnected-(P1-Pad10)") (class "Default")
      (node (ref "P1") (pin "10") (pinfunction "10_10") (pintype "passive"))
    )
    (net (code "56") (name "unconnected-(U2-P1.1{slash}TA0.2{slash}TA1CLK{slash}CDOUT{slash}A1{slash}CD1{slash}VEREF+-Pad2)") (class "Default")
      (node (ref "U2") (pin "2") (pinfunction "P1.1/TA0.2/TA1CLK/CDOUT/A1/CD1/VEREF+_2") (pintype "bidirectional"))
    )
    (net (code "57") (name "unconnected-(U2-P1.3{slash}TA1.2{slash}UCB0STE{slash}A3{slash}CD3-Pad8)") (class "Default")
      (node (ref "U2") (pin "8") (pinfunction "P1.3/TA1.2/UCB0STE/A3/CD3_8") (pintype "bidirectional"))
    )
    (net (code "58") (name "unconnected-(U2-P2.7-Pad33)") (class "Default")
      (node (ref "U2") (pin "33") (pinfunction "P2.7_33") (pintype "bidirectional"))
    )
    (net (code "59") (name "unconnected-(U2-P3.1{slash}A13{slash}CD13-Pad5)") (class "Default")
      (node (ref "U2") (pin "5") (pinfunction "P3.1/A13/CD13_5") (pintype "bidirectional"))
    )
    (net (code "60") (name "unconnected-(U2-P3.2{slash}A14{slash}CD14-Pad6)") (class "Default")
      (node (ref "U2") (pin "6") (pinfunction "P3.2/A14/CD14_6") (pintype "bidirectional"))
    )
    (net (code "61") (name "unconnected-(U2-P3.7{slash}TB2.2-Pad27)") (class "Default")
      (node (ref "U2") (pin "27") (pinfunction "P3.7/TB2.2_27") (pintype "bidirectional"))
    )
    (net (code "62") (name "unconnected-(U2-PJ.4{slash}XIN-Pad37)") (class "Default")
      (node (ref "U2") (pin "37") (pinfunction "PJ.4/XIN_37") (pintype "bidirectional"))
    )
    (net (code "63") (name "unconnected-(U2-PJ.5{slash}XOUT-Pad38)") (class "Default")
      (node (ref "U2") (pin "38") (pinfunction "PJ.5/XOUT_38") (pintype "bidirectional"))
    )
    (net (code "64") (name "unconnected-(U3-HB-Pad4)") (class "Default")
      (node (ref "U3") (pin "4") (pinfunction "HB_4") (pintype "bidirectional"))
    )
    (net (code "65") (name "unconnected-(U3-LA-Pad2)") (class "Default")
      (node (ref "U3") (pin "2") (pinfunction "LA_2") (pintype "bidirectional"))
    )
    (net (code "66") (name "unconnected-(U3-LB-Pad5)") (class "Default")
      (node (ref "U3") (pin "5") (pinfunction "LB_5") (pintype "bidirectional"))
    )
    (net (code "67") (name "unconnected-(U3-WB-Pad6)") (class "Default")
      (node (ref "U3") (pin "6") (pinfunction "WB_6") (pintype "bidirectional"))
    )
    (net (code "68") (name "unconnected-(U4-EN-Pad3)") (class "Default")
      (node (ref "U4") (pin "3") (pinfunction "EN_3") (pintype "passive"))
    )
    (net (code "69") (name "unconnected-(U4-NC-Pad4)") (class "Default")
      (node (ref "U4") (pin "4") (pinfunction "NC_4") (pintype "passive"))
    )
  )
)
